# 4_ETHERNET.net
KiCad netlist of a schematic drawn in Altium Designer
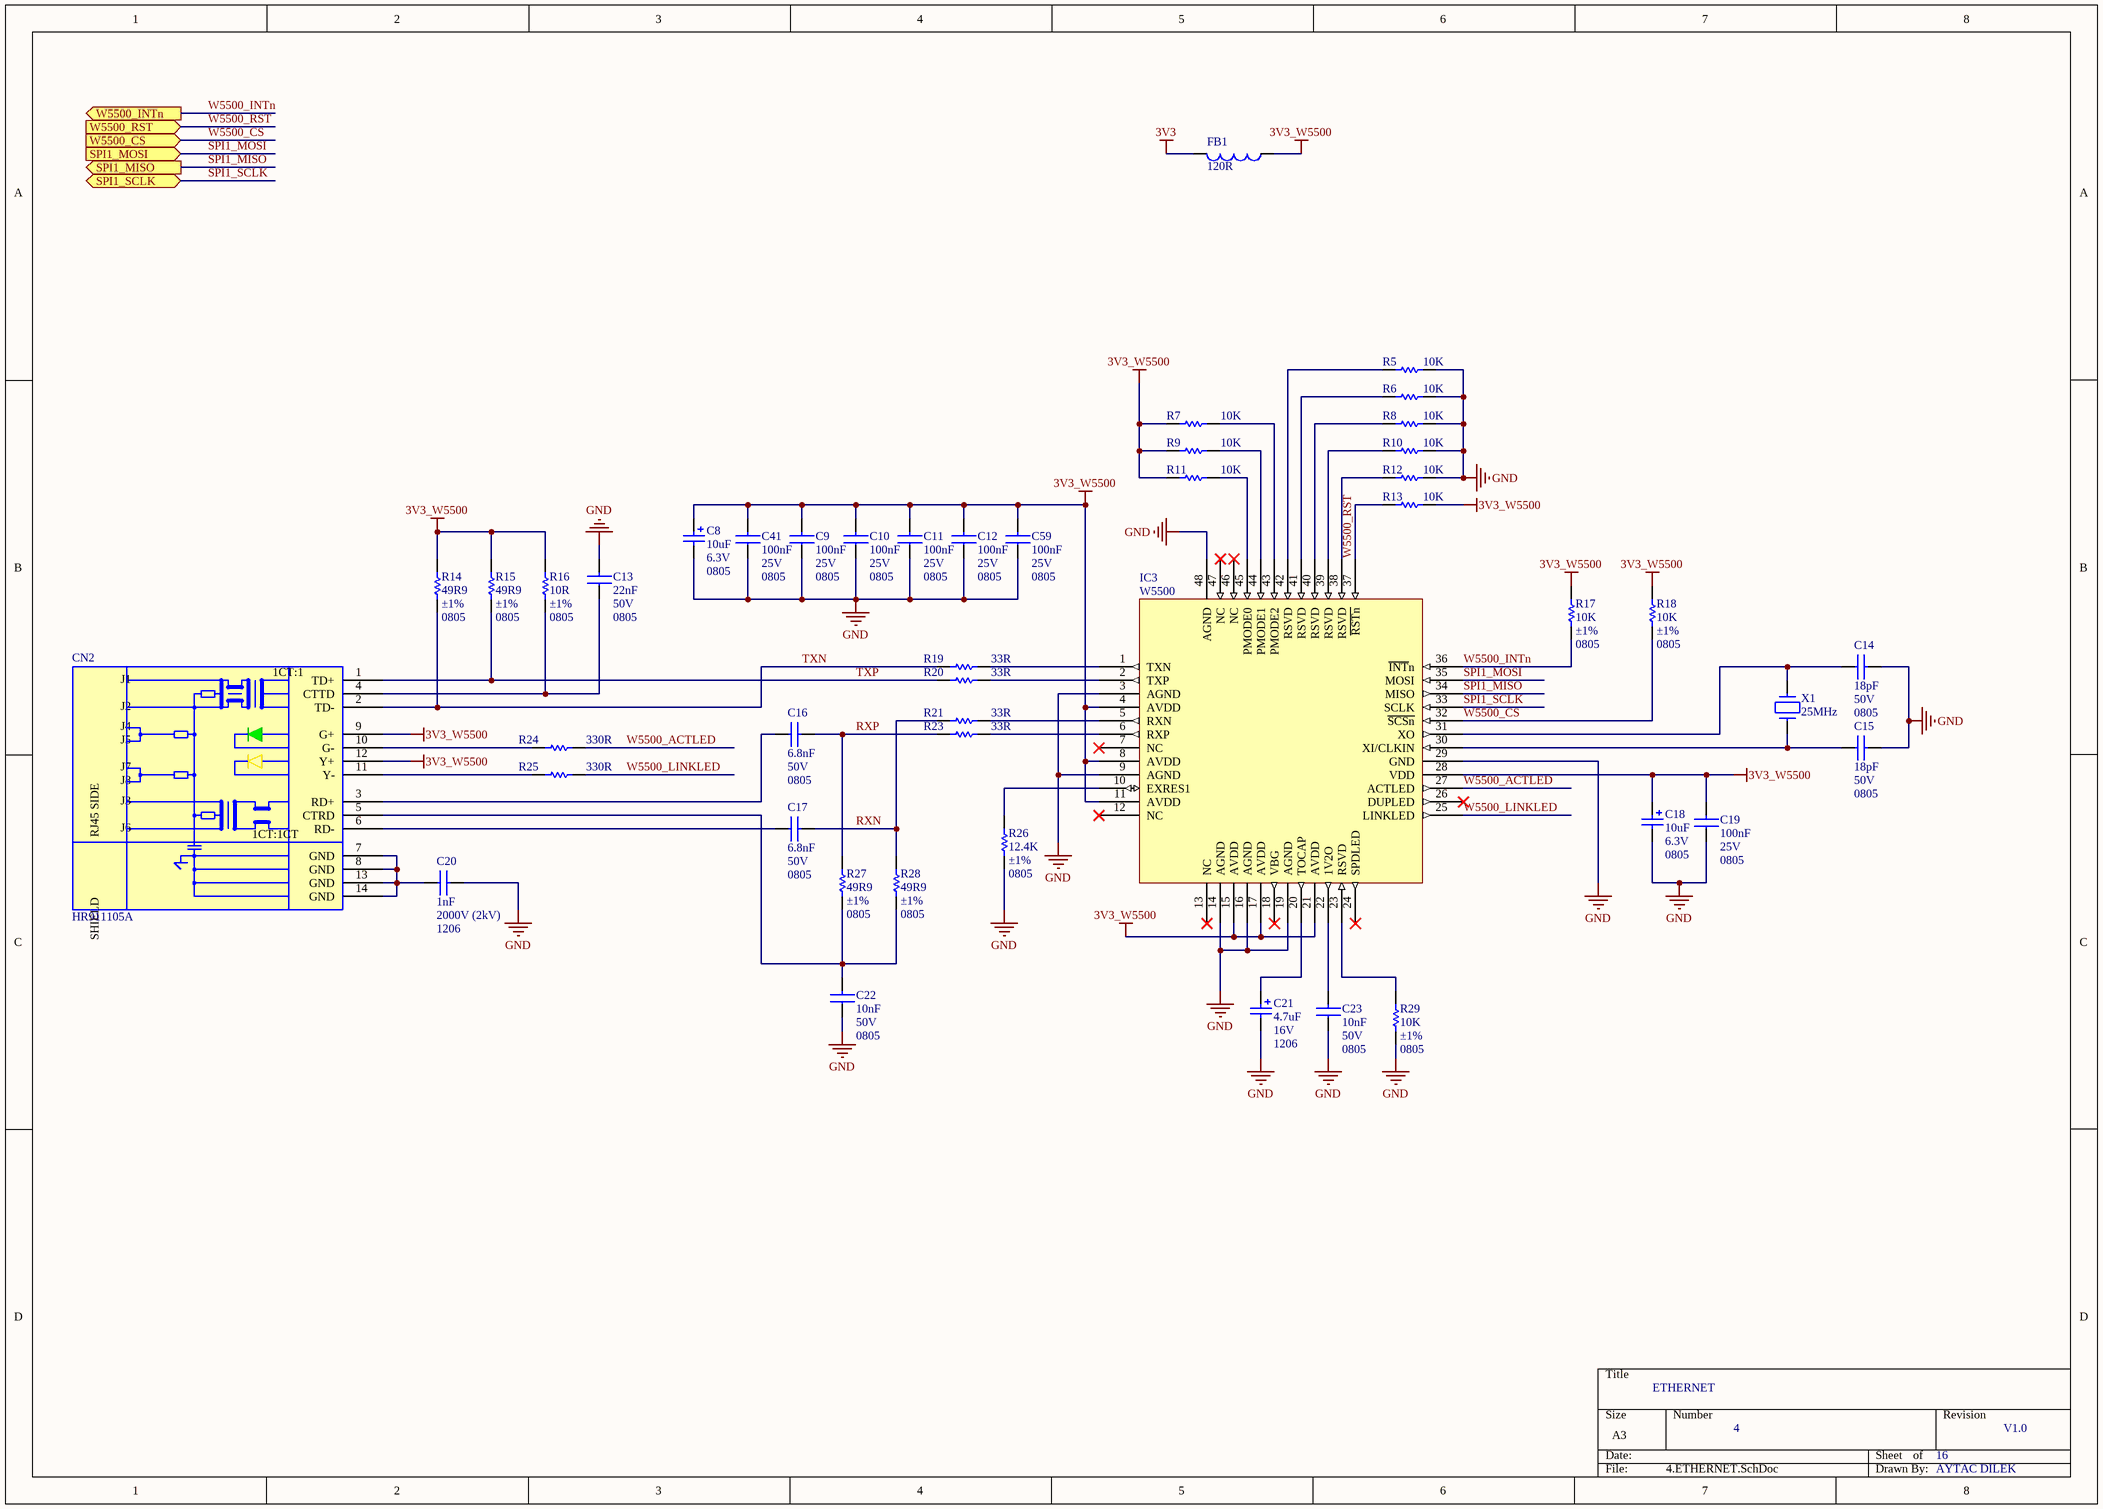
[diagram p0: 4.ETHERNET.SchDoc]

(export (version "E")
  (design (tool "Eeschema 10.0.6"))
  (components
    (comp (ref "C8")
      (value "10uF")
      (footprint "CAPMP2013X12N_EIA-0805_CASE-R")
      (description "CAP TANT 10UF 6.3V 10% 0805")
      (fields
        (field (name "PART NUMBER") "SCAP01400004")
        (field (name "TOLERANCE") "±10%")
        (field (name "VOLTAGE - RATED") "6.3V")
        (field (name "PACKAGE / CASE") "0805")
      )
      (libsource (lib "ComponentDatabase") (part "CAP_P"))
    )
    (comp (ref "C9")
      (value "CAP_NP")
      (footprint "CAPC2012X100N_EIA0805")
      (description "CAP CER 0.1UF 25V X7R 0805")
      (fields
        (field (name "PART NUMBER") "SCAP00300093")
        (field (name "CAPACITANCE") "100nF")
        (field (name "TOLERANCE") "±10%")
        (field (name "VOLTAGE - RATED") "25V")
        (field (name "PACKAGE / CASE") "0805")
      )
      (libsource (lib "ComponentDatabase") (part "CAP_NP"))
    )
    (comp (ref "C10")
      (value "CAP_NP")
      (footprint "CAPC2012X100N_EIA0805")
      (description "CAP CER 0.1UF 25V X7R 0805")
      (fields
        (field (name "PART NUMBER") "SCAP00300093")
        (field (name "CAPACITANCE") "100nF")
        (field (name "TOLERANCE") "±10%")
        (field (name "VOLTAGE - RATED") "25V")
        (field (name "PACKAGE / CASE") "0805")
      )
      (libsource (lib "ComponentDatabase") (part "CAP_NP"))
    )
    (comp (ref "C11")
      (value "CAP_NP")
      (footprint "CAPC2012X100N_EIA0805")
      (description "CAP CER 0.1UF 25V X7R 0805")
      (fields
        (field (name "PART NUMBER") "SCAP00300093")
        (field (name "CAPACITANCE") "100nF")
        (field (name "TOLERANCE") "±10%")
        (field (name "VOLTAGE - RATED") "25V")
        (field (name "PACKAGE / CASE") "0805")
      )
      (libsource (lib "ComponentDatabase") (part "CAP_NP"))
    )
    (comp (ref "C12")
      (value "CAP_NP")
      (footprint "CAPC2012X100N_EIA0805")
      (description "CAP CER 0.1UF 25V X7R 0805")
      (fields
        (field (name "PART NUMBER") "SCAP00300093")
        (field (name "CAPACITANCE") "100nF")
        (field (name "TOLERANCE") "±10%")
        (field (name "VOLTAGE - RATED") "25V")
        (field (name "PACKAGE / CASE") "0805")
      )
      (libsource (lib "ComponentDatabase") (part "CAP_NP"))
    )
    (comp (ref "C13")
      (value "CAP_NP")
      (footprint "CAPC2012X100N_EIA0805")
      (description "CAP CER 0.022UF 50V X7R 0805")
      (fields
        (field (name "PART NUMBER") "SCAP00300087")
        (field (name "CAPACITANCE") "22nF")
        (field (name "TOLERANCE") "±10%")
        (field (name "VOLTAGE - RATED") "50V")
        (field (name "PACKAGE / CASE") "0805")
      )
      (libsource (lib "ComponentDatabase") (part "CAP_NP"))
    )
    (comp (ref "C14")
      (value "CAP_NP")
      (footprint "CAPC2012X100N_EIA0805")
      (description "CAP CER 18PF 50V NP0 0805")
      (fields
        (field (name "PART NUMBER") "SCAP00300040")
        (field (name "CAPACITANCE") "18pF")
        (field (name "TOLERANCE") "±5%")
        (field (name "VOLTAGE - RATED") "50V")
        (field (name "PACKAGE / CASE") "0805")
      )
      (libsource (lib "ComponentDatabase") (part "CAP_NP"))
    )
    (comp (ref "C15")
      (value "CAP_NP")
      (footprint "CAPC2012X100N_EIA0805")
      (description "CAP CER 18PF 50V NP0 0805")
      (fields
        (field (name "PART NUMBER") "SCAP00300040")
        (field (name "CAPACITANCE") "18pF")
        (field (name "TOLERANCE") "±5%")
        (field (name "VOLTAGE - RATED") "50V")
        (field (name "PACKAGE / CASE") "0805")
      )
      (libsource (lib "ComponentDatabase") (part "CAP_NP"))
    )
    (comp (ref "C16")
      (value "CAP_NP")
      (footprint "CAPC2012X100N_EIA0805")
      (description "CAP CER 6800PF 50V X7R 0805")
      (fields
        (field (name "PART NUMBER") "SCAP00300083")
        (field (name "CAPACITANCE") "6.8nF")
        (field (name "TOLERANCE") "±10%")
        (field (name "VOLTAGE - RATED") "50V")
        (field (name "PACKAGE / CASE") "0805")
      )
      (libsource (lib "ComponentDatabase") (part "CAP_NP"))
    )
    (comp (ref "C17")
      (value "CAP_NP")
      (footprint "CAPC2012X100N_EIA0805")
      (description "CAP CER 6800PF 50V X7R 0805")
      (fields
        (field (name "PART NUMBER") "SCAP00300083")
        (field (name "CAPACITANCE") "6.8nF")
        (field (name "TOLERANCE") "±10%")
        (field (name "VOLTAGE - RATED") "50V")
        (field (name "PACKAGE / CASE") "0805")
      )
      (libsource (lib "ComponentDatabase") (part "CAP_NP"))
    )
    (comp (ref "C18")
      (value "10uF")
      (footprint "CAPMP2013X12N_EIA-0805_CASE-R")
      (description "CAP TANT 10UF 6.3V 10% 0805")
      (fields
        (field (name "PART NUMBER") "SCAP01400004")
        (field (name "TOLERANCE") "±10%")
        (field (name "VOLTAGE - RATED") "6.3V")
        (field (name "PACKAGE / CASE") "0805")
      )
      (libsource (lib "ComponentDatabase") (part "CAP_P"))
    )
    (comp (ref "C19")
      (value "CAP_NP")
      (footprint "CAPC2012X100N_EIA0805")
      (description "CAP CER 0.1UF 25V X7R 0805")
      (fields
        (field (name "PART NUMBER") "SCAP00300093")
        (field (name "CAPACITANCE") "100nF")
        (field (name "TOLERANCE") "±10%")
        (field (name "VOLTAGE - RATED") "25V")
        (field (name "PACKAGE / CASE") "0805")
      )
      (libsource (lib "ComponentDatabase") (part "CAP_NP"))
    )
    (comp (ref "C20")
      (value "1nF")
      (footprint "CAPC3216X125N_EIA1206")
      (description "CAP CER 1000PF 2KV X7R 1206")
      (fields
        (field (name "PART NUMBER") "SCAP00410036")
        (field (name "TOLERANCE") "±10%")
        (field (name "VOLTAGE - RATED") "2000V (2kV)")
        (field (name "PACKAGE / CASE") "1206")
      )
      (libsource (lib "ComponentDatabase") (part "CAP_NP"))
    )
    (comp (ref "C21")
      (value "4.7uF")
      (footprint "CAPMP3216X16N_EIA-1206_CASE-A")
      (description "CAP TANT 4.7UF 16V 10% 1206")
      (fields
        (field (name "PART NUMBER") "SCAP01400003")
        (field (name "TOLERANCE") "±10%")
        (field (name "VOLTAGE - RATED") "16V")
        (field (name "PACKAGE / CASE") "1206")
      )
      (libsource (lib "ComponentDatabase") (part "CAP_P"))
    )
    (comp (ref "C22")
      (value "CAP_NP")
      (footprint "CAPC2012X100N_EIA0805")
      (description "CAP CER 10000PF 50V X7R 0805")
      (fields
        (field (name "PART NUMBER") "SCAP00300085")
        (field (name "CAPACITANCE") "10nF")
        (field (name "TOLERANCE") "±10%")
        (field (name "VOLTAGE - RATED") "50V")
        (field (name "PACKAGE / CASE") "0805")
      )
      (libsource (lib "ComponentDatabase") (part "CAP_NP"))
    )
    (comp (ref "C23")
      (value "CAP_NP")
      (footprint "CAPC2012X100N_EIA0805")
      (description "CAP CER 10000PF 50V X7R 0805")
      (fields
        (field (name "PART NUMBER") "SCAP00300085")
        (field (name "CAPACITANCE") "10nF")
        (field (name "TOLERANCE") "±10%")
        (field (name "VOLTAGE - RATED") "50V")
        (field (name "PACKAGE / CASE") "0805")
      )
      (libsource (lib "ComponentDatabase") (part "CAP_NP"))
    )
    (comp (ref "C41")
      (value "CAP_NP")
      (footprint "CAPC2012X100N_EIA0805")
      (description "CAP CER 0.1UF 25V X7R 0805")
      (fields
        (field (name "PART NUMBER") "SCAP00300093")
        (field (name "CAPACITANCE") "100nF")
        (field (name "TOLERANCE") "±10%")
        (field (name "VOLTAGE - RATED") "25V")
        (field (name "PACKAGE / CASE") "0805")
      )
      (libsource (lib "ComponentDatabase") (part "CAP_NP"))
    )
    (comp (ref "C59")
      (value "CAP_NP")
      (footprint "CAPC2012X100N_EIA0805")
      (description "CAP CER 0.1UF 25V X7R 0805")
      (fields
        (field (name "PART NUMBER") "SCAP00300093")
        (field (name "CAPACITANCE") "100nF")
        (field (name "TOLERANCE") "±10%")
        (field (name "VOLTAGE - RATED") "25V")
        (field (name "PACKAGE / CASE") "0805")
      )
      (libsource (lib "ComponentDatabase") (part "CAP_NP"))
    )
    (comp (ref "CN2")
      (value "HR911105A")
      (footprint "HANRUN_HR911105A")
      (description "CONN MAGJACK 1PORT 100 BASE-T")
      (fields (field (name "PART NUMBER") "SCON00127"))
      (libsource (lib "ComponentDatabase") (part "HR911105A"))
    )
    (comp (ref "FB1")
      (value "BEAD")
      (footprint "FILC2012X100N_EIA0805")
      (description "FERRITE CHIP POWER 120 OHM SMD")
      (fields
        (field (name "PART NUMBER") "SFIL00005")
        (field (name "IMPEDANCE") "120R")
        (field (name "MANUFACTURER") "Laird-Signal Integrity Products")
      )
      (libsource (lib "ComponentDatabase") (part "BEAD"))
    )
    (comp (ref "IC3")
      (value "W5500")
      (footprint "QFP50P900X900X160-48N")
      (description "IC CTLR 3-1 ETH TCP/IP 48LQFP")
      (fields
        (field (name "PART NUMBER") "SIC00138")
        (field (name "MANUFACTURER PART NUMBER") "W5500")
        (field (name "MANUFACTURER") "WIZnet")
      )
      (libsource (lib "ComponentDatabase") (part "W5500"))
    )
    (comp (ref "R5")
      (value "10K")
      (footprint "RESC2013X65N_EIA0805")
      (description "RES SMD 10K OHM 1% 1/8W 0805")
      (fields (field (name "PART NUMBER") "SRES03010098") (field (name "TOLERANCE") "±1%"))
      (libsource (lib "ComponentDatabase") (part "RES"))
    )
    (comp (ref "R6")
      (value "10K")
      (footprint "RESC2013X65N_EIA0805")
      (description "RES SMD 10K OHM 1% 1/8W 0805")
      (fields (field (name "PART NUMBER") "SRES03010098") (field (name "TOLERANCE") "±1%"))
      (libsource (lib "ComponentDatabase") (part "RES"))
    )
    (comp (ref "R7")
      (value "10K")
      (footprint "RESC2013X65N_EIA0805")
      (description "RES SMD 10K OHM 1% 1/8W 0805")
      (fields (field (name "PART NUMBER") "SRES03010098") (field (name "TOLERANCE") "±1%"))
      (libsource (lib "ComponentDatabase") (part "RES"))
    )
    (comp (ref "R8")
      (value "10K")
      (footprint "RESC2013X65N_EIA0805")
      (description "RES SMD 10K OHM 1% 1/8W 0805")
      (fields (field (name "PART NUMBER") "SRES03010098") (field (name "TOLERANCE") "±1%"))
      (libsource (lib "ComponentDatabase") (part "RES"))
    )
    (comp (ref "R9")
      (value "10K")
      (footprint "RESC2013X65N_EIA0805")
      (description "RES SMD 10K OHM 1% 1/8W 0805")
      (fields (field (name "PART NUMBER") "SRES03010098") (field (name "TOLERANCE") "±1%"))
      (libsource (lib "ComponentDatabase") (part "RES"))
    )
    (comp (ref "R10")
      (value "10K")
      (footprint "RESC2013X65N_EIA0805")
      (description "RES SMD 10K OHM 1% 1/8W 0805")
      (fields (field (name "PART NUMBER") "SRES03010098") (field (name "TOLERANCE") "±1%"))
      (libsource (lib "ComponentDatabase") (part "RES"))
    )
    (comp (ref "R11")
      (value "10K")
      (footprint "RESC2013X65N_EIA0805")
      (description "RES SMD 10K OHM 1% 1/8W 0805")
      (fields (field (name "PART NUMBER") "SRES03010098") (field (name "TOLERANCE") "±1%"))
      (libsource (lib "ComponentDatabase") (part "RES"))
    )
    (comp (ref "R12")
      (value "10K")
      (footprint "RESC2013X65N_EIA0805")
      (description "RES SMD 10K OHM 1% 1/8W 0805")
      (fields (field (name "PART NUMBER") "SRES03010098") (field (name "TOLERANCE") "±1%"))
      (libsource (lib "ComponentDatabase") (part "RES"))
    )
    (comp (ref "R13")
      (value "10K")
      (footprint "RESC2013X65N_EIA0805")
      (description "RES SMD 10K OHM 1% 1/8W 0805")
      (fields (field (name "PART NUMBER") "SRES03010098") (field (name "TOLERANCE") "±1%"))
      (libsource (lib "ComponentDatabase") (part "RES"))
    )
    (comp (ref "R14")
      (value "49R9")
      (footprint "RESC2013X65N_EIA0805")
      (description "RES SMD 49.9 OHM 1% 1/8W 0805")
      (fields
        (field (name "PART NUMBER") "SRES03030081")
        (field (name "TOLERANCE") "±1%")
        (field (name "PACKAGE / CASE") "0805")
        (field (name "MANUFACTURER") "Samsung Electro-Mechanics America, Inc.")
      )
      (libsource (lib "ComponentDatabase") (part "RES"))
    )
    (comp (ref "R15")
      (value "49R9")
      (footprint "RESC2013X65N_EIA0805")
      (description "RES SMD 49.9 OHM 1% 1/8W 0805")
      (fields
        (field (name "PART NUMBER") "SRES03030081")
        (field (name "TOLERANCE") "±1%")
        (field (name "PACKAGE / CASE") "0805")
        (field (name "MANUFACTURER") "Samsung Electro-Mechanics America, Inc.")
      )
      (libsource (lib "ComponentDatabase") (part "RES"))
    )
    (comp (ref "R16")
      (value "10R")
      (footprint "RESC2013X65N_EIA0805")
      (description "RES SMD 10 OHM 1% 1/8W 0805")
      (fields
        (field (name "PART NUMBER") "SRES03010026")
        (field (name "TOLERANCE") "±1%")
        (field (name "PACKAGE / CASE") "0805")
        (field (name "MANUFACTURER") "Yageo")
      )
      (libsource (lib "ComponentDatabase") (part "RES"))
    )
    (comp (ref "R17")
      (value "10K")
      (footprint "RESC2013X65N_EIA0805")
      (description "RES SMD 10K OHM 1% 1/8W 0805")
      (fields
        (field (name "PART NUMBER") "SRES03010098")
        (field (name "TOLERANCE") "±1%")
        (field (name "PACKAGE / CASE") "0805")
        (field (name "MANUFACTURER") "Yageo")
      )
      (libsource (lib "ComponentDatabase") (part "RES"))
    )
    (comp (ref "R18")
      (value "10K")
      (footprint "RESC2013X65N_EIA0805")
      (description "RES SMD 10K OHM 1% 1/8W 0805")
      (fields
        (field (name "PART NUMBER") "SRES03010098")
        (field (name "TOLERANCE") "±1%")
        (field (name "PACKAGE / CASE") "0805")
        (field (name "MANUFACTURER") "Yageo")
      )
      (libsource (lib "ComponentDatabase") (part "RES"))
    )
    (comp (ref "R19")
      (value "33R")
      (footprint "RESC2013X65N_EIA0805")
      (description "RES SMD 33 OHM 1% 1/8W 0805")
      (fields (field (name "PART NUMBER") "SRES03010038") (field (name "TOLERANCE") "±1%"))
      (libsource (lib "ComponentDatabase") (part "RES"))
    )
    (comp (ref "R20")
      (value "33R")
      (footprint "RESC2013X65N_EIA0805")
      (description "RES SMD 33 OHM 1% 1/8W 0805")
      (fields (field (name "PART NUMBER") "SRES03010038") (field (name "TOLERANCE") "±1%"))
      (libsource (lib "ComponentDatabase") (part "RES"))
    )
    (comp (ref "R21")
      (value "33R")
      (footprint "RESC2013X65N_EIA0805")
      (description "RES SMD 33 OHM 1% 1/8W 0805")
      (fields (field (name "PART NUMBER") "SRES03010038") (field (name "TOLERANCE") "±1%"))
      (libsource (lib "ComponentDatabase") (part "RES"))
    )
    (comp (ref "R23")
      (value "33R")
      (footprint "RESC2013X65N_EIA0805")
      (description "RES SMD 33 OHM 1% 1/8W 0805")
      (fields (field (name "PART NUMBER") "SRES03010038") (field (name "TOLERANCE") "±1%"))
      (libsource (lib "ComponentDatabase") (part "RES"))
    )
    (comp (ref "R24")
      (value "330R")
      (footprint "RESC2013X65N_EIA0805")
      (description "RES SMD 330 OHM 1% 1/8W 0805")
      (fields (field (name "PART NUMBER") "SRES03010062") (field (name "TOLERANCE") "±1%"))
      (libsource (lib "ComponentDatabase") (part "RES"))
    )
    (comp (ref "R25")
      (value "330R")
      (footprint "RESC2013X65N_EIA0805")
      (description "RES SMD 330 OHM 1% 1/8W 0805")
      (fields (field (name "PART NUMBER") "SRES03010062") (field (name "TOLERANCE") "±1%"))
      (libsource (lib "ComponentDatabase") (part "RES"))
    )
    (comp (ref "R26")
      (value "12.4K")
      (footprint "RESC2013X65N_EIA0805")
      (description "RES SMD 12.4K OHM 1% 1/8W 0805")
      (fields
        (field (name "PART NUMBER") "SRES03010171")
        (field (name "TOLERANCE") "±1%")
        (field (name "PACKAGE / CASE") "0805")
        (field (name "MANUFACTURER") "Yageo")
      )
      (libsource (lib "ComponentDatabase") (part "RES"))
    )
    (comp (ref "R27")
      (value "49R9")
      (footprint "RESC2013X65N_EIA0805")
      (description "RES SMD 49.9 OHM 1% 1/8W 0805")
      (fields
        (field (name "PART NUMBER") "SRES03030081")
        (field (name "TOLERANCE") "±1%")
        (field (name "PACKAGE / CASE") "0805")
        (field (name "MANUFACTURER") "Samsung Electro-Mechanics America, Inc.")
      )
      (libsource (lib "ComponentDatabase") (part "RES"))
    )
    (comp (ref "R28")
      (value "49R9")
      (footprint "RESC2013X65N_EIA0805")
      (description "RES SMD 49.9 OHM 1% 1/8W 0805")
      (fields
        (field (name "PART NUMBER") "SRES03030081")
        (field (name "TOLERANCE") "±1%")
        (field (name "PACKAGE / CASE") "0805")
        (field (name "MANUFACTURER") "Samsung Electro-Mechanics America, Inc.")
      )
      (libsource (lib "ComponentDatabase") (part "RES"))
    )
    (comp (ref "R29")
      (value "10K")
      (footprint "RESC2013X65N_EIA0805")
      (description "RES SMD 10K OHM 1% 1/8W 0805")
      (fields
        (field (name "PART NUMBER") "SRES03010098")
        (field (name "TOLERANCE") "±1%")
        (field (name "PACKAGE / CASE") "0805")
        (field (name "MANUFACTURER") "Yageo")
      )
      (libsource (lib "ComponentDatabase") (part "RES"))
    )
    (comp (ref "X1")
      (value "25MHz")
      (footprint "HC-49/US")
      (description "CRYSTAL 25.0000MHZ 18PF T/H")
      (fields (field (name "PART NUMBER") "SCRY00016") (field (name "MANUFACTURER") "CTS-Frequency Controls"))
      (libsource (lib "ComponentDatabase") (part "CRYSTAL"))
    )
  )
  (nets
    (net (code "1") (name "/RXN") (class "Default")
      (node (ref "C17") (pin "2") (pinfunction "2_2") (pintype "passive"))
      (node (ref "R21") (pin "2") (pinfunction "2_2") (pintype "passive"))
      (node (ref "R28") (pin "1") (pinfunction "1_1") (pintype "passive"))
    )
    (net (code "2") (name "/RXP") (class "Default")
      (node (ref "C16") (pin "2") (pinfunction "2_2") (pintype "passive"))
      (node (ref "R23") (pin "2") (pinfunction "2_2") (pintype "passive"))
      (node (ref "R27") (pin "1") (pinfunction "1_1") (pintype "passive"))
    )
    (net (code "3") (name "/SPI1_MISO") (class "Default")
      (node (ref "IC3") (pin "34") (pinfunction "MISO_34") (pintype "output"))
    )
    (net (code "4") (name "/SPI1_MOSI") (class "Default")
      (node (ref "IC3") (pin "35") (pinfunction "MOSI_35") (pintype "input"))
    )
    (net (code "5") (name "/SPI1_SCLK") (class "Default")
      (node (ref "IC3") (pin "33") (pinfunction "SCLK_33") (pintype "input"))
    )
    (net (code "6") (name "/TXN") (class "Default")
      (node (ref "CN2") (pin "2") (pinfunction "TD-_2") (pintype "passive"))
      (node (ref "R14") (pin "2") (pinfunction "2_2") (pintype "passive"))
      (node (ref "R19") (pin "2") (pinfunction "2_2") (pintype "passive"))
    )
    (net (code "7") (name "/TXP") (class "Default")
      (node (ref "CN2") (pin "1") (pinfunction "TD+_1") (pintype "passive"))
      (node (ref "R15") (pin "2") (pinfunction "2_2") (pintype "passive"))
      (node (ref "R20") (pin "2") (pinfunction "2_2") (pintype "passive"))
    )
    (net (code "8") (name "/W5500_ACTLED") (class "Default")
      (node (ref "IC3") (pin "27") (pinfunction "ACTLED_27") (pintype "output"))
      (node (ref "R24") (pin "1") (pinfunction "1_1") (pintype "passive"))
    )
    (net (code "9") (name "/W5500_CS") (class "Default")
      (node (ref "IC3") (pin "32") (pinfunction "~{SCSn}_32") (pintype "input"))
      (node (ref "R18") (pin "2") (pinfunction "2_2") (pintype "passive"))
    )
    (net (code "10") (name "/W5500_INTn") (class "Default")
      (node (ref "IC3") (pin "36") (pinfunction "~{INT}n_36") (pintype "input"))
      (node (ref "R17") (pin "2") (pinfunction "2_2") (pintype "passive"))
    )
    (net (code "11") (name "/W5500_LINKLED") (class "Default")
      (node (ref "IC3") (pin "25") (pinfunction "LINKLED_25") (pintype "output"))
      (node (ref "R25") (pin "1") (pinfunction "1_1") (pintype "passive"))
    )
    (net (code "12") (name "/W5500_RST") (class "Default")
      (node (ref "IC3") (pin "37") (pinfunction "~{RSTn}_37") (pintype "input"))
      (node (ref "R13") (pin "1") (pinfunction "1_1") (pintype "passive"))
    )
    (net (code "13") (name "3V3") (class "Default")
      (node (ref "FB1") (pin "2") (pinfunction "2_2") (pintype "passive"))
    )
    (net (code "14") (name "3V3_W5500") (class "Default")
      (node (ref "C10") (pin "2") (pinfunction "2_2") (pintype "passive"))
      (node (ref "C11") (pin "2") (pinfunction "2_2") (pintype "passive"))
      (node (ref "C12") (pin "2") (pinfunction "2_2") (pintype "passive"))
      (node (ref "C18") (pin "1") (pinfunction "1_1") (pintype "passive"))
      (node (ref "C19") (pin "2") (pinfunction "2_2") (pintype "passive"))
      (node (ref "C41") (pin "2") (pinfunction "2_2") (pintype "passive"))
      (node (ref "C59") (pin "2") (pinfunction "2_2") (pintype "passive"))
      (node (ref "C8") (pin "1") (pinfunction "1_1") (pintype "passive"))
      (node (ref "C9") (pin "2") (pinfunction "2_2") (pintype "passive"))
      (node (ref "CN2") (pin "12") (pinfunction "Y+_12") (pintype "passive"))
      (node (ref "CN2") (pin "9") (pinfunction "G+_9") (pintype "passive"))
      (node (ref "FB1") (pin "1") (pinfunction "1_1") (pintype "passive"))
      (node (ref "IC3") (pin "11") (pinfunction "AVDD_11") (pintype "power_in"))
      (node (ref "IC3") (pin "15") (pinfunction "AVDD_15") (pintype "power_in"))
      (node (ref "IC3") (pin "17") (pinfunction "AVDD_17") (pintype "power_in"))
      (node (ref "IC3") (pin "21") (pinfunction "AVDD_21") (pintype "power_in"))
      (node (ref "IC3") (pin "28") (pinfunction "VDD_28") (pintype "power_in"))
      (node (ref "IC3") (pin "4") (pinfunction "AVDD_4") (pintype "power_in"))
      (node (ref "IC3") (pin "8") (pinfunction "AVDD_8") (pintype "power_in"))
      (node (ref "R11") (pin "2") (pinfunction "2_2") (pintype "passive"))
      (node (ref "R13") (pin "2") (pinfunction "2_2") (pintype "passive"))
      (node (ref "R14") (pin "1") (pinfunction "1_1") (pintype "passive"))
      (node (ref "R15") (pin "1") (pinfunction "1_1") (pintype "passive"))
      (node (ref "R16") (pin "1") (pinfunction "1_1") (pintype "passive"))
      (node (ref "R17") (pin "1") (pinfunction "1_1") (pintype "passive"))
      (node (ref "R18") (pin "1") (pinfunction "1_1") (pintype "passive"))
      (node (ref "R7") (pin "2") (pinfunction "2_2") (pintype "passive"))
      (node (ref "R9") (pin "2") (pinfunction "2_2") (pintype "passive"))
    )
    (net (code "15") (name "GND") (class "Default")
      (node (ref "C10") (pin "1") (pinfunction "1_1") (pintype "passive"))
      (node (ref "C11") (pin "1") (pinfunction "1_1") (pintype "passive"))
      (node (ref "C12") (pin "1") (pinfunction "1_1") (pintype "passive"))
      (node (ref "C13") (pin "2") (pinfunction "2_2") (pintype "passive"))
      (node (ref "C14") (pin "2") (pinfunction "2_2") (pintype "passive"))
      (node (ref "C15") (pin "2") (pinfunction "2_2") (pintype "passive"))
      (node (ref "C18") (pin "2") (pinfunction "2_2") (pintype "passive"))
      (node (ref "C19") (pin "1") (pinfunction "1_1") (pintype "passive"))
      (node (ref "C20") (pin "2") (pinfunction "2_2") (pintype "passive"))
      (node (ref "C21") (pin "2") (pinfunction "2_2") (pintype "passive"))
      (node (ref "C22") (pin "1") (pinfunction "1_1") (pintype "passive"))
      (node (ref "C23") (pin "1") (pinfunction "1_1") (pintype "passive"))
      (node (ref "C41") (pin "1") (pinfunction "1_1") (pintype "passive"))
      (node (ref "C59") (pin "1") (pinfunction "1_1") (pintype "passive"))
      (node (ref "C8") (pin "2") (pinfunction "2_2") (pintype "passive"))
      (node (ref "C9") (pin "1") (pinfunction "1_1") (pintype "passive"))
      (node (ref "IC3") (pin "14") (pinfunction "AGND_14") (pintype "power_in"))
      (node (ref "IC3") (pin "16") (pinfunction "AGND_16") (pintype "power_in"))
      (node (ref "IC3") (pin "19") (pinfunction "AGND_19") (pintype "power_in"))
      (node (ref "IC3") (pin "29") (pinfunction "GND_29") (pintype "power_in"))
      (node (ref "IC3") (pin "3") (pinfunction "AGND_3") (pintype "power_in"))
      (node (ref "IC3") (pin "48") (pinfunction "AGND_48") (pintype "power_in"))
      (node (ref "IC3") (pin "9") (pinfunction "AGND_9") (pintype "power_in"))
      (node (ref "R10") (pin "2") (pinfunction "2_2") (pintype "passive"))
      (node (ref "R12") (pin "2") (pinfunction "2_2") (pintype "passive"))
      (node (ref "R26") (pin "2") (pinfunction "2_2") (pintype "passive"))
      (node (ref "R29") (pin "2") (pinfunction "2_2") (pintype "passive"))
      (node (ref "R5") (pin "2") (pinfunction "2_2") (pintype "passive"))
      (node (ref "R6") (pin "2") (pinfunction "2_2") (pintype "passive"))
      (node (ref "R8") (pin "2") (pinfunction "2_2") (pintype "passive"))
    )
    (net (code "16") (name "Net-(C20-Pad1)") (class "Default")
      (node (ref "C20") (pin "1") (pinfunction "1_1") (pintype "passive"))
      (node (ref "CN2") (pin "13") (pinfunction "GND_13") (pintype "power_in"))
      (node (ref "CN2") (pin "14") (pinfunction "GND_14") (pintype "power_in"))
      (node (ref "CN2") (pin "7") (pinfunction "GND_7") (pintype "power_in"))
      (node (ref "CN2") (pin "8") (pinfunction "GND_8") (pintype "power_in"))
    )
    (net (code "17") (name "Net-(CN2-CTRD)") (class "Default")
      (node (ref "C22") (pin "2") (pinfunction "2_2") (pintype "passive"))
      (node (ref "CN2") (pin "5") (pinfunction "CTRD_5") (pintype "passive"))
      (node (ref "R27") (pin "2") (pinfunction "2_2") (pintype "passive"))
      (node (ref "R28") (pin "2") (pinfunction "2_2") (pintype "passive"))
    )
    (net (code "18") (name "Net-(CN2-CTTD)") (class "Default")
      (node (ref "C13") (pin "1") (pinfunction "1_1") (pintype "passive"))
      (node (ref "CN2") (pin "4") (pinfunction "CTTD_4") (pintype "passive"))
      (node (ref "R16") (pin "2") (pinfunction "2_2") (pintype "passive"))
    )
    (net (code "19") (name "Net-(CN2-G-)") (class "Default")
      (node (ref "CN2") (pin "10") (pinfunction "G-_10") (pintype "passive"))
      (node (ref "R24") (pin "2") (pinfunction "2_2") (pintype "passive"))
    )
    (net (code "20") (name "Net-(CN2-RD+)") (class "Default")
      (node (ref "C16") (pin "1") (pinfunction "1_1") (pintype "passive"))
      (node (ref "CN2") (pin "3") (pinfunction "RD+_3") (pintype "passive"))
    )
    (net (code "21") (name "Net-(CN2-RD-)") (class "Default")
      (node (ref "C17") (pin "1") (pinfunction "1_1") (pintype "passive"))
      (node (ref "CN2") (pin "6") (pinfunction "RD-_6") (pintype "passive"))
    )
    (net (code "22") (name "Net-(CN2-Y-)") (class "Default")
      (node (ref "CN2") (pin "11") (pinfunction "Y-_11") (pintype "passive"))
      (node (ref "R25") (pin "2") (pinfunction "2_2") (pintype "passive"))
    )
    (net (code "23") (name "Net-(IC3-1V2O)") (class "Default")
      (node (ref "C23") (pin "2") (pinfunction "2_2") (pintype "passive"))
      (node (ref "IC3") (pin "22") (pinfunction "1V2O_22") (pintype "output"))
    )
    (net (code "24") (name "Net-(IC3-EXRES1)") (class "Default")
      (node (ref "IC3") (pin "10") (pinfunction "EXRES1_10") (pintype "bidirectional"))
      (node (ref "R26") (pin "1") (pinfunction "1_1") (pintype "passive"))
    )
    (net (code "25") (name "Net-(IC3-PMODE0)") (class "Default")
      (node (ref "IC3") (pin "45") (pinfunction "PMODE0_45") (pintype "input"))
      (node (ref "R11") (pin "1") (pinfunction "1_1") (pintype "passive"))
    )
    (net (code "26") (name "Net-(IC3-PMODE1)") (class "Default")
      (node (ref "IC3") (pin "44") (pinfunction "PMODE1_44") (pintype "input"))
      (node (ref "R9") (pin "1") (pinfunction "1_1") (pintype "passive"))
    )
    (net (code "27") (name "Net-(IC3-PMODE2)") (class "Default")
      (node (ref "IC3") (pin "43") (pinfunction "PMODE2_43") (pintype "input"))
      (node (ref "R7") (pin "1") (pinfunction "1_1") (pintype "passive"))
    )
    (net (code "28") (name "Net-(IC3-RSVD-Pad23)") (class "Default")
      (node (ref "IC3") (pin "23") (pinfunction "RSVD_23") (pintype "input"))
      (node (ref "R29") (pin "1") (pinfunction "1_1") (pintype "passive"))
    )
    (net (code "29") (name "Net-(IC3-RSVD-Pad38)") (class "Default")
      (node (ref "IC3") (pin "38") (pinfunction "RSVD_38") (pintype "input"))
      (node (ref "R12") (pin "1") (pinfunction "1_1") (pintype "passive"))
    )
    (net (code "30") (name "Net-(IC3-RSVD-Pad39)") (class "Default")
      (node (ref "IC3") (pin "39") (pinfunction "RSVD_39") (pintype "input"))
      (node (ref "R10") (pin "1") (pinfunction "1_1") (pintype "passive"))
    )
    (net (code "31") (name "Net-(IC3-RSVD-Pad40)") (class "Default")
      (node (ref "IC3") (pin "40") (pinfunction "RSVD_40") (pintype "input"))
      (node (ref "R8") (pin "1") (pinfunction "1_1") (pintype "passive"))
    )
    (net (code "32") (name "Net-(IC3-RSVD-Pad41)") (class "Default")
      (node (ref "IC3") (pin "41") (pinfunction "RSVD_41") (pintype "input"))
      (node (ref "R6") (pin "1") (pinfunction "1_1") (pintype "passive"))
    )
    (net (code "33") (name "Net-(IC3-RSVD-Pad42)") (class "Default")
      (node (ref "IC3") (pin "42") (pinfunction "RSVD_42") (pintype "input"))
      (node (ref "R5") (pin "1") (pinfunction "1_1") (pintype "passive"))
    )
    (net (code "34") (name "Net-(IC3-RXN)") (class "Default")
      (node (ref "IC3") (pin "5") (pinfunction "RXN_5") (pintype "output"))
      (node (ref "R21") (pin "1") (pinfunction "1_1") (pintype "passive"))
    )
    (net (code "35") (name "Net-(IC3-RXP)") (class "Default")
      (node (ref "IC3") (pin "6") (pinfunction "RXP_6") (pintype "output"))
      (node (ref "R23") (pin "1") (pinfunction "1_1") (pintype "passive"))
    )
    (net (code "36") (name "Net-(IC3-TOCAP)") (class "Default")
      (node (ref "C21") (pin "1") (pinfunction "1_1") (pintype "passive"))
      (node (ref "IC3") (pin "20") (pinfunction "TOCAP_20") (pintype "output"))
    )
    (net (code "37") (name "Net-(IC3-TXN)") (class "Default")
      (node (ref "IC3") (pin "1") (pinfunction "TXN_1") (pintype "output"))
      (node (ref "R19") (pin "1") (pinfunction "1_1") (pintype "passive"))
    )
    (net (code "38") (name "Net-(IC3-TXP)") (class "Default")
      (node (ref "IC3") (pin "2") (pinfunction "TXP_2") (pintype "output"))
      (node (ref "R20") (pin "1") (pinfunction "1_1") (pintype "passive"))
    )
    (net (code "39") (name "Net-(IC3-XI{slash}CLKIN)") (class "Default")
      (node (ref "C15") (pin "1") (pinfunction "1_1") (pintype "passive"))
      (node (ref "IC3") (pin "30") (pinfunction "XI/CLKIN_30") (pintype "input"))
      (node (ref "X1") (pin "2") (pinfunction "2_2") (pintype "passive"))
    )
    (net (code "40") (name "Net-(IC3-XO)") (class "Default")
      (node (ref "C14") (pin "1") (pinfunction "1_1") (pintype "passive"))
      (node (ref "IC3") (pin "31") (pinfunction "XO_31") (pintype "output"))
      (node (ref "X1") (pin "1") (pinfunction "1_1") (pintype "passive"))
    )
    (net (code "41") (name "unconnected-(IC3-DUPLED-Pad26)") (class "Default")
      (node (ref "IC3") (pin "26") (pinfunction "DUPLED_26") (pintype "output+no_connect"))
    )
    (net (code "42") (name "unconnected-(IC3-NC-Pad7)") (class "Default")
      (node (ref "IC3") (pin "7") (pinfunction "NC_7") (pintype "passive+no_connect"))
    )
    (net (code "43") (name "unconnected-(IC3-NC-Pad12)") (class "Default")
      (node (ref "IC3") (pin "12") (pinfunction "NC_12") (pintype "passive+no_connect"))
    )
    (net (code "44") (name "unconnected-(IC3-NC-Pad13)") (class "Default")
      (node (ref "IC3") (pin "13") (pinfunction "NC_13") (pintype "passive+no_connect"))
    )
    (net (code "45") (name "unconnected-(IC3-NC-Pad46)") (class "Default")
      (node (ref "IC3") (pin "46") (pinfunction "NC_46") (pintype "input+no_connect"))
    )
    (net (code "46") (name "unconnected-(IC3-NC-Pad47)") (class "Default")
      (node (ref "IC3") (pin "47") (pinfunction "NC_47") (pintype "input+no_connect"))
    )
    (net (code "47") (name "unconnected-(IC3-SPDLED-Pad24)") (class "Default")
      (node (ref "IC3") (pin "24") (pinfunction "SPDLED_24") (pintype "output+no_connect"))
    )
    (net (code "48") (name "unconnected-(IC3-VBG-Pad18)") (class "Default")
      (node (ref "IC3") (pin "18") (pinfunction "VBG_18") (pintype "output+no_connect"))
    )
  )
)
